# QUTMS-TSAL-V01-S00.net
KiCad netlist of a schematic drawn in Altium Designer
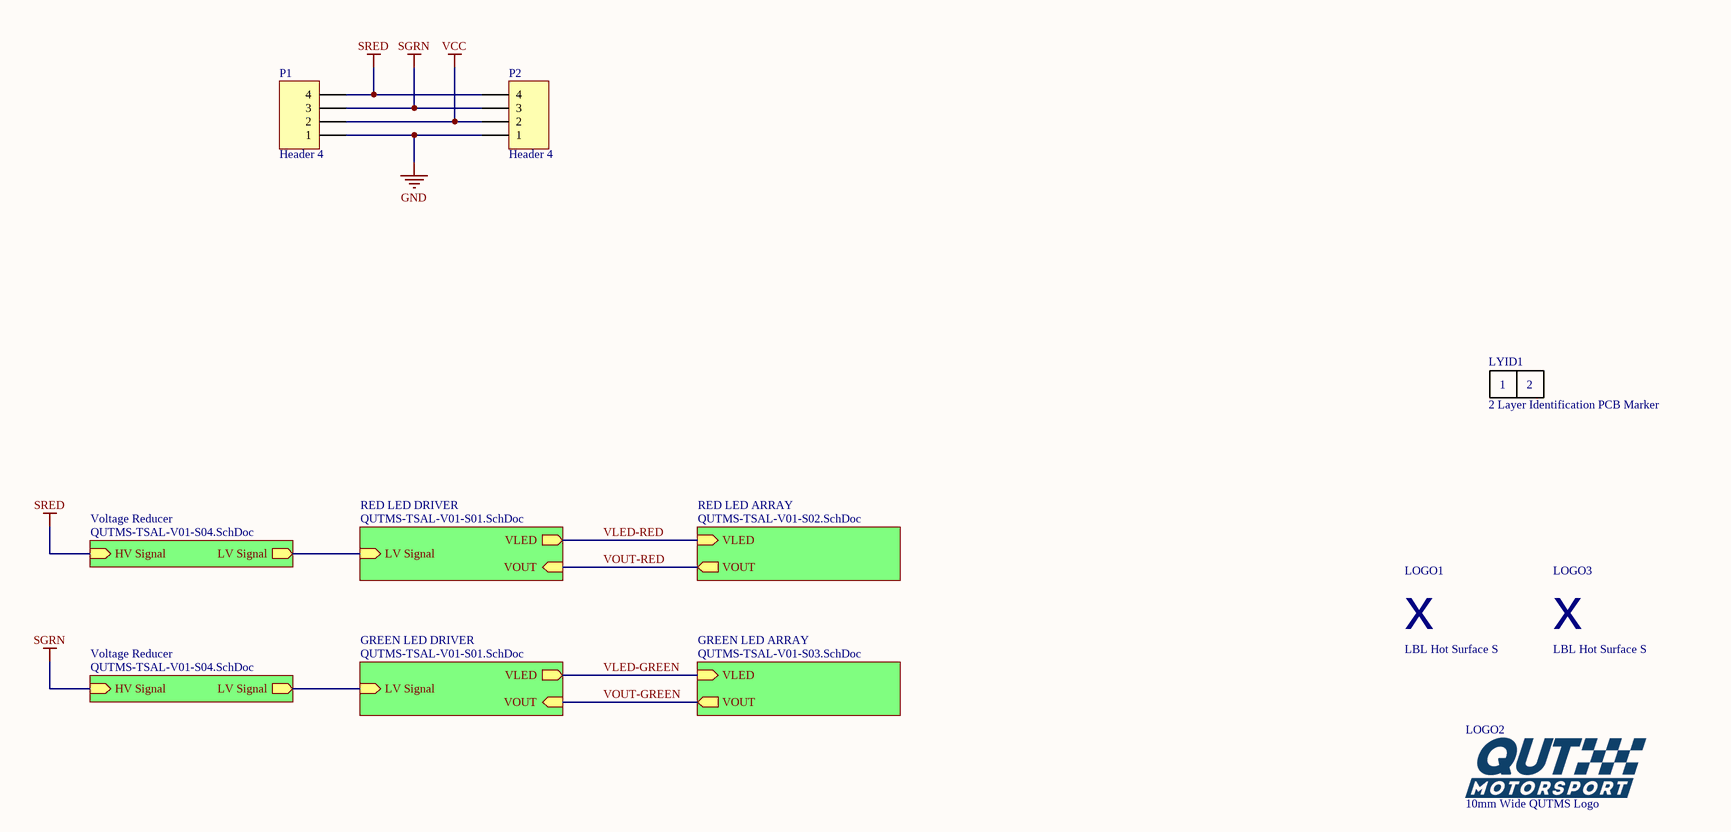
[diagram p0: QUTMS-TSAL-V01-S00.SchDoc]

(export (version "E")
  (design (tool "Eeschema 10.0.6"))
  (components
    (comp (ref "LOGO1")
      (value "LBL Hot Surface S")
      (footprint "LBL HOT SMALL")
      (libsource (lib "QUTMS_PCBLibrary") (part "LBL Hot Surface S"))
    )
    (comp (ref "LOGO2")
      (value "10mm Wide QUTMS Logo")
      (footprint "QUTMS LOGO 10MM")
      (libsource (lib "QUTMS_PCBLibrary") (part "QUTMS Logo 10mm"))
    )
    (comp (ref "LOGO3")
      (value "LBL Hot Surface S")
      (footprint "LBL HOT SMALL")
      (libsource (lib "QUTMS_PCBLibrary") (part "LBL Hot Surface S"))
    )
    (comp (ref "LYID1")
      (value "2 Layer Identification PCB Marker")
      (footprint "LAYER IDENT 2")
      (libsource (lib "QUTMS_PCBLibrary") (part "Layer Identification 2"))
    )
    (comp (ref "P1")
      (value "Header 4")
      (footprint "HDR1X4")
      (description "Header, 4-Pin")
      (fields (field (name "PUBLISHER") "Altium Limited"))
      (libsource (lib "") (part "Header 4_1"))
    )
    (comp (ref "P2")
      (value "Header 4")
      (footprint "HDR1X4")
      (description "Header, 4-Pin")
      (fields (field (name "PUBLISHER") "Altium Limited"))
      (libsource (lib "Miscellaneous Connectors") (part "Header 4"))
    )
  )
  (nets
    (net (code "7") (name "GND") (class "Default")
      (node (ref "P1") (pin "1") (pinfunction "1_1") (pintype "passive"))
      (node (ref "P2") (pin "1") (pinfunction "1_1") (pintype "passive"))
    )
    (net (code "8") (name "SGRN") (class "Default")
      (node (ref "P1") (pin "3") (pinfunction "3_3") (pintype "passive"))
      (node (ref "P2") (pin "3") (pinfunction "3_3") (pintype "passive"))
    )
    (net (code "9") (name "SRED") (class "Default")
      (node (ref "P1") (pin "4") (pinfunction "4_4") (pintype "passive"))
      (node (ref "P2") (pin "4") (pinfunction "4_4") (pintype "passive"))
    )
    (net (code "10") (name "VCC") (class "Default")
      (node (ref "P1") (pin "2") (pinfunction "2_2") (pintype "passive"))
      (node (ref "P2") (pin "2") (pinfunction "2_2") (pintype "passive"))
    )
  )
)
